# OutputChannel.net
KiCad netlist of a schematic drawn in Altium Designer
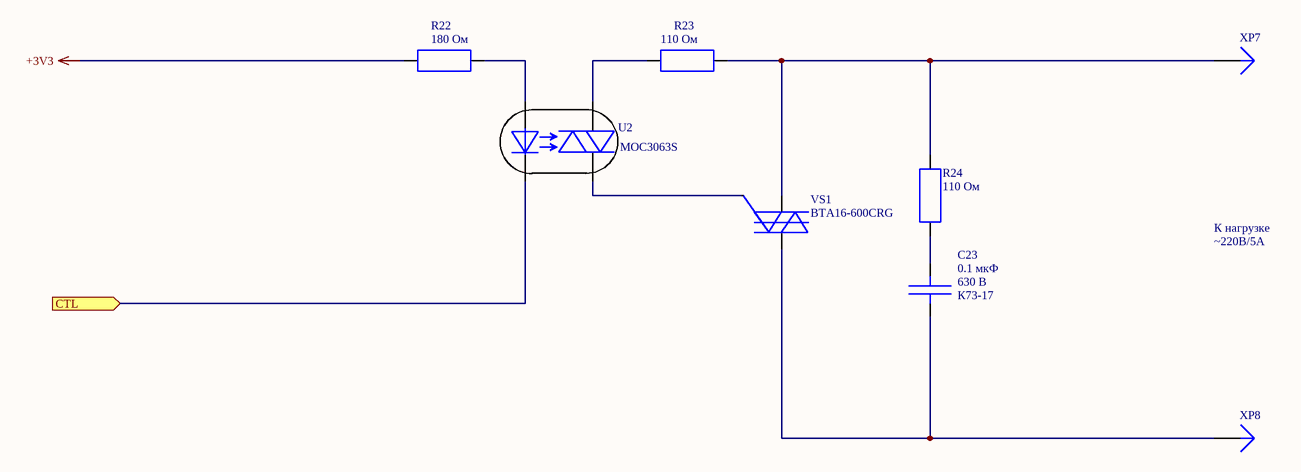
[diagram p0: OutputChannel.SchDoc]

(export (version "E")
  (design (tool "Eeschema 10.0.6"))
  (components
    (comp (ref "C23")
      (value "0.1 мкФ")
      (footprint "B32652A6-7-12.5-18")
      (description "Конденсатор")
      (fields (field (name "VOLTAGE") "630 В") (field (name "TYPE") "К73-17") (field (name "Comment") "Cap"))
      (libsource (lib "GOST_Generic") (part "Cap"))
    )
    (comp (ref "R22")
      (value "180 Ом")
      (footprint "RES_0603-1608")
      (description "ЧИП резистор постоянный")
      (fields (field (name "POWER") "0.1 W") (field (name "TOLERANCE") "5%"))
      (libsource (lib "GOST_Generic") (part "Res"))
    )
    (comp (ref "R23")
      (value "110 Ом")
      (footprint "RES_2512-6332")
      (description "ЧИП резистор постоянный")
      (fields (field (name "POWER") "2 W") (field (name "TOLERANCE") "5%"))
      (libsource (lib "GOST_Generic") (part "Res"))
    )
    (comp (ref "R24")
      (value "110 Ом")
      (footprint "RES_2512-6332")
      (description "ЧИП резистор постоянный")
      (fields (field (name "POWER") "2 W") (field (name "TOLERANCE") "5%"))
      (libsource (lib "GOST_Generic") (part "Res"))
    )
    (comp (ref "U2")
      (value "OptoIso_Triac")
      (footprint "SMD-2.54-6")
      (description "Оптопара симисторная")
      (fields (field (name "TYPE") "MOC3063S"))
      (libsource (lib "GOST_Generic") (part "OptoIso_Triac"))
    )
    (comp (ref "VS1")
      (value "Diode_TRIAC")
      (footprint "TO-220FP")
      (description "Тиристор триодный симметричный двунаправленный")
      (fields (field (name "TYPE") "BTA16-600CRG"))
      (libsource (lib "GOST_Generic") (part "Diode_TRIAC"))
    )
    (comp (ref "XP7")
      (value "Plug")
      (footprint "EK508V_Pin")
      (fields (field (name "PUBLISHER") "Altium Limited"))
      (libsource (lib "Miscellaneous Connectors") (part "Plug"))
    )
    (comp (ref "XP8")
      (value "Plug")
      (footprint "EK508V_Pin")
      (fields (field (name "PUBLISHER") "Altium Limited"))
      (libsource (lib "Miscellaneous Connectors") (part "Plug"))
    )
  )
  (nets
    (net (code "1") (name "+3V3") (class "Default") (node (ref "R22") (pin "2") (pintype "passive")))
    (net (code "2") (name "/CTL") (class "Default")
      (node (ref "U2") (pin "2") (pinfunction "K1_2") (pintype "passive"))
    )
    (net (code "3") (name "Net-(C23-Pad2)") (class "Default")
      (node (ref "C23") (pin "2") (pinfunction "2_2") (pintype "passive"))
      (node (ref "R24") (pin "2") (pintype "passive"))
    )
    (net (code "4") (name "Net-(U2-A1)") (class "Default")
      (node (ref "R22") (pin "1") (pintype "passive"))
      (node (ref "U2") (pin "1") (pinfunction "A1_1") (pintype "passive"))
    )
    (net (code "5") (name "Net-(U2-A2)") (class "Default")
      (node (ref "R23") (pin "2") (pintype "passive"))
      (node (ref "U2") (pin "3") (pinfunction "A2_3") (pintype "passive"))
    )
    (net (code "6") (name "Net-(U2-K2)") (class "Default")
      (node (ref "U2") (pin "4") (pinfunction "K2_4") (pintype "passive"))
      (node (ref "VS1") (pin "3") (pinfunction "G_3") (pintype "passive"))
    )
    (net (code "7") (name "Net-(VS1-A)") (class "Default")
      (node (ref "C23") (pin "1") (pinfunction "1_1") (pintype "passive"))
      (node (ref "VS1") (pin "1") (pinfunction "A_1") (pintype "passive"))
      (node (ref "XP8") (pin "1") (pinfunction "1_1") (pintype "passive"))
    )
    (net (code "8") (name "Net-(VS1-K)") (class "Default")
      (node (ref "R23") (pin "1") (pintype "passive"))
      (node (ref "R24") (pin "1") (pintype "passive"))
      (node (ref "VS1") (pin "2") (pinfunction "K_2") (pintype "passive"))
      (node (ref "XP7") (pin "1") (pinfunction "1_1") (pintype "passive"))
    )
  )
)
